# watchplb_gps_v1_1.net
KiCad netlist of a schematic drawn in EAGLE
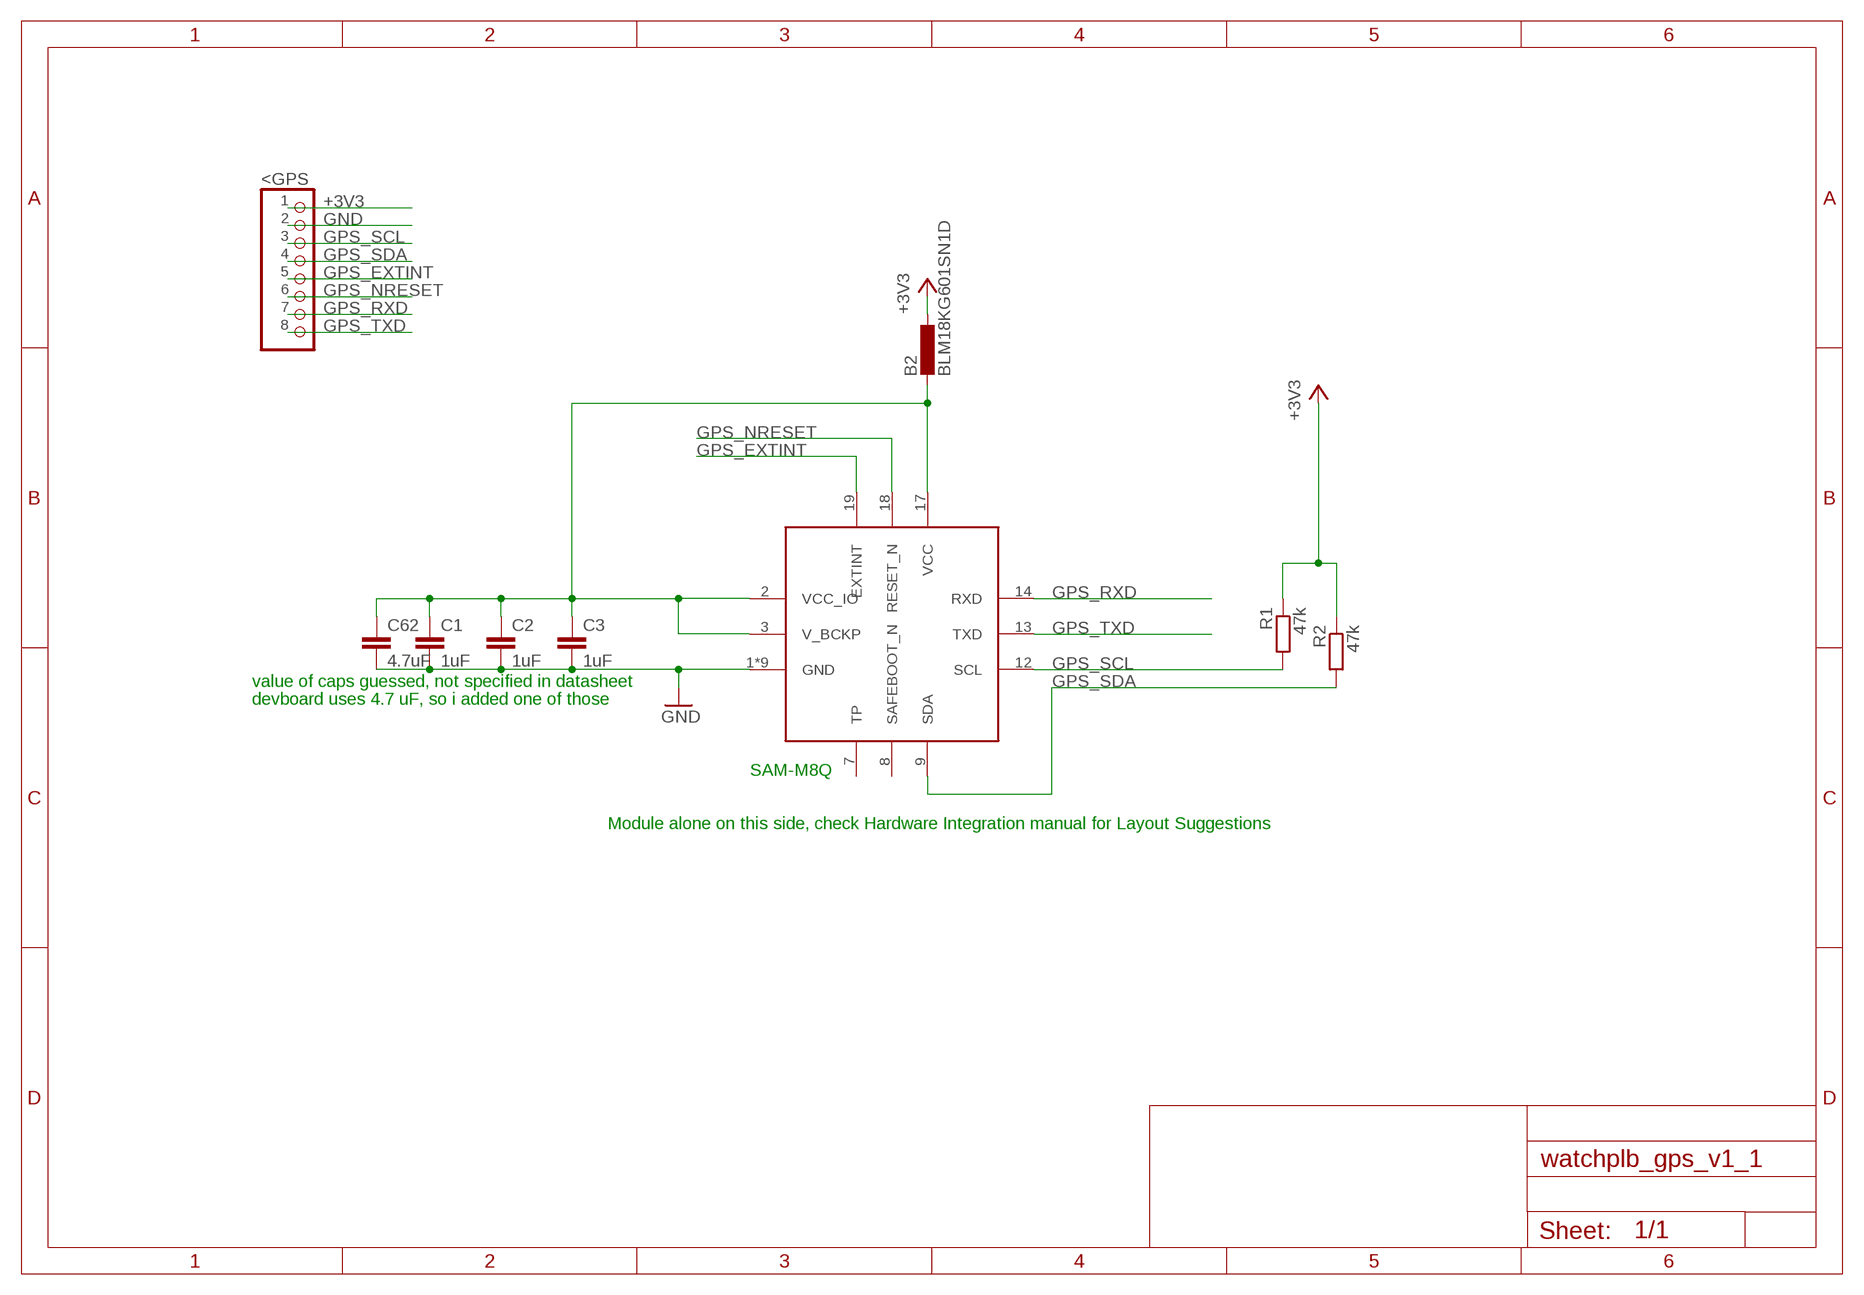
[diagram p0: schematic, sheet 1]

(export (version "E")
  (design (tool "Eeschema 10.0.6"))
  (components
    (comp (ref "<GPS")
      (value "PINHD-1X8")
      (footprint "eagle-import:1X08")
      (libsource (lib "eagle-import") (part "PINHD-1X8"))
    )
    (comp (ref "B2")
      (value "BLM18KG601SN1D")
      (footprint "eagle-import:L0603")
      (libsource (lib "eagle-import") (part "B-EU_B0603"))
    )
    (comp (ref "C1")
      (value "1uF")
      (footprint "eagle-import:C0805")
      (libsource (lib "eagle-import") (part "C-EUC0805"))
    )
    (comp (ref "C2")
      (value "1uF")
      (footprint "eagle-import:C0805")
      (libsource (lib "eagle-import") (part "C-EUC0805"))
    )
    (comp (ref "C3")
      (value "1uF")
      (footprint "eagle-import:C0805")
      (libsource (lib "eagle-import") (part "C-EUC0805"))
    )
    (comp (ref "C62")
      (value "4.7uF")
      (footprint "eagle-import:C0805")
      (libsource (lib "eagle-import") (part "C-EUC0805"))
    )
    (comp (ref "IC1")
      (value "SAM-M8Q")
      (footprint "eagle-import:SAM-M8Q")
      (libsource (lib "eagle-import") (part "SAM-M8Q"))
    )
    (comp (ref "R1")
      (value "47k")
      (footprint "eagle-import:M0805")
      (libsource (lib "eagle-import") (part "R-EU_M0805"))
    )
    (comp (ref "R2")
      (value "47k")
      (footprint "eagle-import:M0805")
      (libsource (lib "eagle-import") (part "R-EU_M0805"))
    )
  )
  (nets
    (net (code "1") (name "+3V3") (class "Default")
      (node (ref "<GPS") (pin "1") (pinfunction "1_1") (pintype "passive"))
      (node (ref "B2") (pin "1") (pinfunction "1_1") (pintype "passive"))
      (node (ref "R1") (pin "1") (pinfunction "1_1") (pintype "passive"))
      (node (ref "R2") (pin "1") (pinfunction "1_1") (pintype "passive"))
    )
    (net (code "2") (name "/GPS_EXTINT") (class "Default")
      (node (ref "<GPS") (pin "5") (pinfunction "5_5") (pintype "passive"))
      (node (ref "IC1") (pin "19") (pinfunction "EXTINT_19") (pintype "bidirectional"))
    )
    (net (code "3") (name "/GPS_NRESET") (class "Default")
      (node (ref "<GPS") (pin "6") (pinfunction "6_6") (pintype "passive"))
      (node (ref "IC1") (pin "18") (pinfunction "RESET_N_18") (pintype "bidirectional"))
    )
    (net (code "4") (name "/GPS_RXD") (class "Default")
      (node (ref "<GPS") (pin "7") (pinfunction "7_7") (pintype "passive"))
      (node (ref "IC1") (pin "14") (pinfunction "RXD_14") (pintype "bidirectional"))
    )
    (net (code "5") (name "/GPS_SCL") (class "Default")
      (node (ref "<GPS") (pin "3") (pinfunction "3_3") (pintype "passive"))
      (node (ref "IC1") (pin "12") (pinfunction "SCL_12") (pintype "bidirectional"))
      (node (ref "R1") (pin "2") (pinfunction "2_2") (pintype "passive"))
    )
    (net (code "6") (name "/GPS_SDA") (class "Default")
      (node (ref "<GPS") (pin "4") (pinfunction "4_4") (pintype "passive"))
      (node (ref "IC1") (pin "9") (pinfunction "SDA_9") (pintype "bidirectional"))
      (node (ref "R2") (pin "2") (pinfunction "2_2") (pintype "passive"))
    )
    (net (code "7") (name "/GPS_TXD") (class "Default")
      (node (ref "<GPS") (pin "8") (pinfunction "8_8") (pintype "passive"))
      (node (ref "IC1") (pin "13") (pinfunction "TXD_13") (pintype "bidirectional"))
    )
    (net (code "8") (name "GND") (class "Default")
      (node (ref "<GPS") (pin "2") (pinfunction "2_2") (pintype "passive"))
      (node (ref "C1") (pin "2") (pinfunction "2_2") (pintype "passive"))
      (node (ref "C2") (pin "2") (pinfunction "2_2") (pintype "passive"))
      (node (ref "C3") (pin "2") (pinfunction "2_2") (pintype "passive"))
      (node (ref "C62") (pin "2") (pinfunction "2_2") (pintype "passive"))
      (node (ref "IC1") (pin "1") (pinfunction "GND_1") (pintype "bidirectional"))
      (node (ref "IC1") (pin "10") (pinfunction "GND_10") (pintype "bidirectional"))
      (node (ref "IC1") (pin "11") (pinfunction "GND_11") (pintype "bidirectional"))
      (node (ref "IC1") (pin "15") (pinfunction "GND_15") (pintype "bidirectional"))
      (node (ref "IC1") (pin "16") (pinfunction "GND_16") (pintype "bidirectional"))
      (node (ref "IC1") (pin "20") (pinfunction "GND_20") (pintype "bidirectional"))
      (node (ref "IC1") (pin "4") (pinfunction "GND_4") (pintype "bidirectional"))
      (node (ref "IC1") (pin "5") (pinfunction "GND_5") (pintype "bidirectional"))
      (node (ref "IC1") (pin "6") (pinfunction "GND_6") (pintype "bidirectional"))
    )
    (net (code "9") (name "Net-(IC1-VCC)") (class "Default")
      (node (ref "B2") (pin "2") (pinfunction "2_2") (pintype "passive"))
      (node (ref "C1") (pin "1") (pinfunction "1_1") (pintype "passive"))
      (node (ref "C2") (pin "1") (pinfunction "1_1") (pintype "passive"))
      (node (ref "C3") (pin "1") (pinfunction "1_1") (pintype "passive"))
      (node (ref "C62") (pin "1") (pinfunction "1_1") (pintype "passive"))
      (node (ref "IC1") (pin "17") (pinfunction "VCC_17") (pintype "bidirectional"))
      (node (ref "IC1") (pin "2") (pinfunction "VCC_IO_2") (pintype "bidirectional"))
      (node (ref "IC1") (pin "3") (pinfunction "V_BCKP_3") (pintype "bidirectional"))
    )
    (net (code "10") (name "unconnected-(IC1-SAFEBOOT_N-Pad8)") (class "Default")
      (node (ref "IC1") (pin "8") (pinfunction "SAFEBOOT_N_8") (pintype "bidirectional"))
    )
    (net (code "11") (name "unconnected-(IC1-TP-Pad7)") (class "Default")
      (node (ref "IC1") (pin "7") (pinfunction "TP_7") (pintype "bidirectional"))
    )
  )
)
